# TE0719.net
KiCad netlist of a schematic drawn in Altium Designer
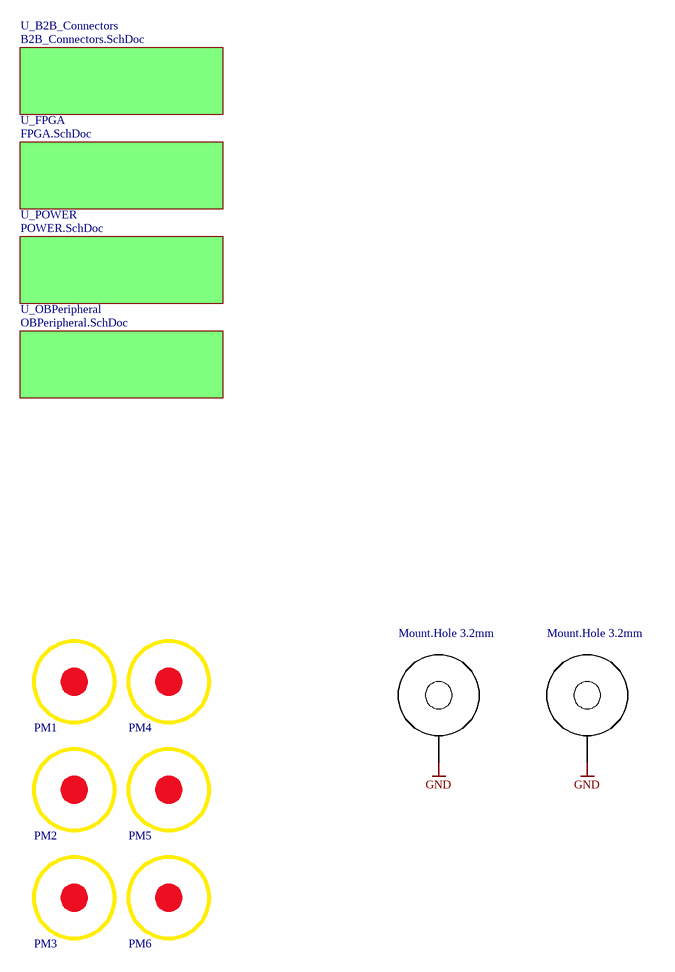
[diagram p0: TE0719.SchDoc]

(export (version "E")
  (design (tool "Eeschema 10.0.6"))
  (components
    (comp (ref "H1")
      (value "Mount.Hole 3.2mm")
      (footprint "MHole3_2mm")
      (libsource (lib "TE") (part "MHole"))
    )
    (comp (ref "H4")
      (value "Mount.Hole 3.2mm")
      (footprint "MHole3_2mm")
      (libsource (lib "TE") (part "MHole"))
    )
    (comp (ref "PM1")
      (value "FIDU-DOT - small")
      (footprint "FIDU-DOT - small")
      (description "FIDU-DOT - SMALL")
      (libsource (lib "TE") (part "FIDU-DOT - small"))
    )
    (comp (ref "PM2")
      (value "FIDU-DOT - small")
      (footprint "FIDU-DOT - small")
      (description "FIDU-DOT - SMALL")
      (libsource (lib "TE") (part "FIDU-DOT - small"))
    )
    (comp (ref "PM3")
      (value "FIDU-DOT - small")
      (footprint "FIDU-DOT - small")
      (description "FIDU-DOT - SMALL")
      (libsource (lib "TE") (part "FIDU-DOT - small"))
    )
    (comp (ref "PM4")
      (value "FIDU-DOT - small")
      (footprint "FIDU-DOT - small")
      (description "FIDU-DOT - SMALL")
      (libsource (lib "TE") (part "FIDU-DOT - small"))
    )
    (comp (ref "PM5")
      (value "FIDU-DOT - small")
      (footprint "FIDU-DOT - small")
      (description "FIDU-DOT - SMALL")
      (libsource (lib "TE") (part "FIDU-DOT - small"))
    )
    (comp (ref "PM6")
      (value "FIDU-DOT - small")
      (footprint "FIDU-DOT - small")
      (description "FIDU-DOT - SMALL")
      (libsource (lib "TE") (part "FIDU-DOT - small"))
    )
  )
  (nets
    (net (code "1") (name "GND") (class "Default")
      (node (ref "H1") (pin "1") (pinfunction "1_1") (pintype "passive"))
      (node (ref "H4") (pin "1") (pinfunction "1_1") (pintype "passive"))
    )
  )
)
